# Sheet_ConnectA10.net
KiCad netlist of a schematic drawn in Altium Designer
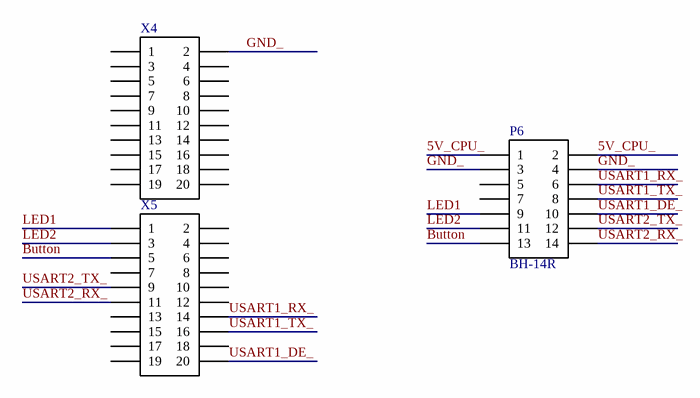
[diagram p0: Sheet_ConnectA10.SchDoc]

(export (version "E")
  (design (tool "Eeschema 10.0.6"))
  (components
    (comp (ref "P6")
      (value "BH-14R")
      (footprint "BH-14R")
      (description "IDC/BH")
      (fields (field (name "PUBLISHER") "Altium Limited"))
      (libsource (lib "Connect") (part "BH-14"))
    )
    (comp (ref "X4")
      (value "PBD2-20")
      (footprint "PBD2-1.27-20-SMD")
      (description "Header, 20-Pin")
      (libsource (lib "Connect") (part "PBD2-20"))
    )
    (comp (ref "X5")
      (value "PBD2-20")
      (footprint "PBD2-1.27-20-SMD")
      (description "Header, 20-Pin")
      (libsource (lib "Connect") (part "PBD2-20"))
    )
  )
  (nets
    (net (code "1") (name "/5V_CPU_") (class "Default")
      (node (ref "P6") (pin "1") (pinfunction "1_1") (pintype "passive"))
      (node (ref "P6") (pin "2") (pinfunction "2_2") (pintype "passive"))
    )
    (net (code "2") (name "/Button") (class "Default")
      (node (ref "P6") (pin "13") (pinfunction "13_13") (pintype "passive"))
      (node (ref "X5") (pin "5") (pinfunction "5_5") (pintype "passive"))
    )
    (net (code "3") (name "/GND_") (class "Default")
      (node (ref "P6") (pin "3") (pinfunction "3_3") (pintype "passive"))
      (node (ref "P6") (pin "4") (pinfunction "4_4") (pintype "passive"))
      (node (ref "X4") (pin "2") (pinfunction "2_2") (pintype "passive"))
    )
    (net (code "4") (name "/LED1") (class "Default")
      (node (ref "P6") (pin "9") (pinfunction "9_9") (pintype "passive"))
      (node (ref "X5") (pin "1") (pinfunction "1_1") (pintype "passive"))
    )
    (net (code "5") (name "/LED2") (class "Default")
      (node (ref "P6") (pin "11") (pinfunction "11_11") (pintype "passive"))
      (node (ref "X5") (pin "3") (pinfunction "3_3") (pintype "passive"))
    )
    (net (code "6") (name "/USART1_DE_") (class "Default")
      (node (ref "P6") (pin "10") (pinfunction "10_10") (pintype "passive"))
      (node (ref "X5") (pin "20") (pinfunction "20_20") (pintype "passive"))
    )
    (net (code "7") (name "/USART1_RX_") (class "Default")
      (node (ref "P6") (pin "6") (pinfunction "6_6") (pintype "passive"))
      (node (ref "X5") (pin "14") (pinfunction "14_14") (pintype "passive"))
    )
    (net (code "8") (name "/USART1_TX_") (class "Default")
      (node (ref "P6") (pin "8") (pinfunction "8_8") (pintype "passive"))
      (node (ref "X5") (pin "16") (pinfunction "16_16") (pintype "passive"))
    )
    (net (code "9") (name "/USART2_RX_") (class "Default")
      (node (ref "P6") (pin "14") (pinfunction "14_14") (pintype "passive"))
      (node (ref "X5") (pin "11") (pinfunction "11_11") (pintype "passive"))
    )
    (net (code "10") (name "/USART2_TX_") (class "Default")
      (node (ref "P6") (pin "12") (pinfunction "12_12") (pintype "passive"))
      (node (ref "X5") (pin "9") (pinfunction "9_9") (pintype "passive"))
    )
    (net (code "11") (name "unconnected-(P6-Pad5)") (class "Default")
      (node (ref "P6") (pin "5") (pinfunction "5_5") (pintype "passive"))
    )
    (net (code "12") (name "unconnected-(P6-Pad7)") (class "Default")
      (node (ref "P6") (pin "7") (pinfunction "7_7") (pintype "passive"))
    )
    (net (code "13") (name "unconnected-(X4-Pad1)") (class "Default")
      (node (ref "X4") (pin "1") (pinfunction "1_1") (pintype "passive"))
    )
    (net (code "14") (name "unconnected-(X4-Pad3)") (class "Default")
      (node (ref "X4") (pin "3") (pinfunction "3_3") (pintype "passive"))
    )
    (net (code "15") (name "unconnected-(X4-Pad4)") (class "Default")
      (node (ref "X4") (pin "4") (pinfunction "4_4") (pintype "passive"))
    )
    (net (code "16") (name "unconnected-(X4-Pad5)") (class "Default")
      (node (ref "X4") (pin "5") (pinfunction "5_5") (pintype "passive"))
    )
    (net (code "17") (name "unconnected-(X4-Pad6)") (class "Default")
      (node (ref "X4") (pin "6") (pinfunction "6_6") (pintype "passive"))
    )
    (net (code "18") (name "unconnected-(X4-Pad7)") (class "Default")
      (node (ref "X4") (pin "7") (pinfunction "7_7") (pintype "passive"))
    )
    (net (code "19") (name "unconnected-(X4-Pad8)") (class "Default")
      (node (ref "X4") (pin "8") (pinfunction "8_8") (pintype "passive"))
    )
    (net (code "20") (name "unconnected-(X4-Pad9)") (class "Default")
      (node (ref "X4") (pin "9") (pinfunction "9_9") (pintype "passive"))
    )
    (net (code "21") (name "unconnected-(X4-Pad10)") (class "Default")
      (node (ref "X4") (pin "10") (pinfunction "10_10") (pintype "passive"))
    )
    (net (code "22") (name "unconnected-(X4-Pad11)") (class "Default")
      (node (ref "X4") (pin "11") (pinfunction "11_11") (pintype "passive"))
    )
    (net (code "23") (name "unconnected-(X4-Pad12)") (class "Default")
      (node (ref "X4") (pin "12") (pinfunction "12_12") (pintype "passive"))
    )
    (net (code "24") (name "unconnected-(X4-Pad13)") (class "Default")
      (node (ref "X4") (pin "13") (pinfunction "13_13") (pintype "passive"))
    )
    (net (code "25") (name "unconnected-(X4-Pad14)") (class "Default")
      (node (ref "X4") (pin "14") (pinfunction "14_14") (pintype "passive"))
    )
    (net (code "26") (name "unconnected-(X4-Pad15)") (class "Default")
      (node (ref "X4") (pin "15") (pinfunction "15_15") (pintype "passive"))
    )
    (net (code "27") (name "unconnected-(X4-Pad16)") (class "Default")
      (node (ref "X4") (pin "16") (pinfunction "16_16") (pintype "passive"))
    )
    (net (code "28") (name "unconnected-(X4-Pad17)") (class "Default")
      (node (ref "X4") (pin "17") (pinfunction "17_17") (pintype "passive"))
    )
    (net (code "29") (name "unconnected-(X4-Pad18)") (class "Default")
      (node (ref "X4") (pin "18") (pinfunction "18_18") (pintype "passive"))
    )
    (net (code "30") (name "unconnected-(X4-Pad19)") (class "Default")
      (node (ref "X4") (pin "19") (pinfunction "19_19") (pintype "passive"))
    )
    (net (code "31") (name "unconnected-(X4-Pad20)") (class "Default")
      (node (ref "X4") (pin "20") (pinfunction "20_20") (pintype "passive"))
    )
    (net (code "32") (name "unconnected-(X5-Pad2)") (class "Default")
      (node (ref "X5") (pin "2") (pinfunction "2_2") (pintype "passive"))
    )
    (net (code "33") (name "unconnected-(X5-Pad4)") (class "Default")
      (node (ref "X5") (pin "4") (pinfunction "4_4") (pintype "passive"))
    )
    (net (code "34") (name "unconnected-(X5-Pad6)") (class "Default")
      (node (ref "X5") (pin "6") (pinfunction "6_6") (pintype "passive"))
    )
    (net (code "35") (name "unconnected-(X5-Pad7)") (class "Default")
      (node (ref "X5") (pin "7") (pinfunction "7_7") (pintype "passive"))
    )
    (net (code "36") (name "unconnected-(X5-Pad8)") (class "Default")
      (node (ref "X5") (pin "8") (pinfunction "8_8") (pintype "passive"))
    )
    (net (code "37") (name "unconnected-(X5-Pad10)") (class "Default")
      (node (ref "X5") (pin "10") (pinfunction "10_10") (pintype "passive"))
    )
    (net (code "38") (name "unconnected-(X5-Pad12)") (class "Default")
      (node (ref "X5") (pin "12") (pinfunction "12_12") (pintype "passive"))
    )
    (net (code "39") (name "unconnected-(X5-Pad13)") (class "Default")
      (node (ref "X5") (pin "13") (pinfunction "13_13") (pintype "passive"))
    )
    (net (code "40") (name "unconnected-(X5-Pad15)") (class "Default")
      (node (ref "X5") (pin "15") (pinfunction "15_15") (pintype "passive"))
    )
    (net (code "41") (name "unconnected-(X5-Pad17)") (class "Default")
      (node (ref "X5") (pin "17") (pinfunction "17_17") (pintype "passive"))
    )
    (net (code "42") (name "unconnected-(X5-Pad18)") (class "Default")
      (node (ref "X5") (pin "18") (pinfunction "18_18") (pintype "passive"))
    )
    (net (code "43") (name "unconnected-(X5-Pad19)") (class "Default")
      (node (ref "X5") (pin "19") (pinfunction "19_19") (pintype "passive"))
    )
  )
)
